# BusBreakout_I2C.net
KiCad netlist of a schematic drawn in EAGLE
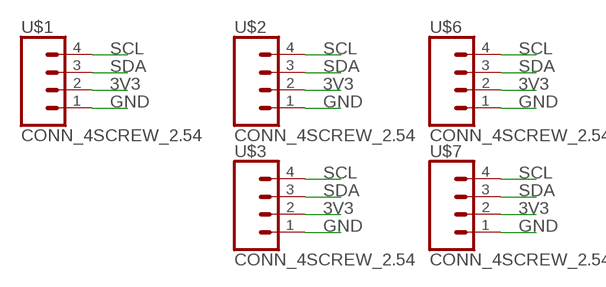
[diagram p0: schematic, sheet 1]

(export (version "E")
  (design (tool "Eeschema 10.0.6"))
  (components
    (comp (ref "U$1")
      (value "CONN_4SCREW_2.54")
      (footprint "eagle-import:1X04")
      (libsource (lib "eagle-import") (part "CONN_4SCREW_2.54"))
    )
    (comp (ref "U$2")
      (value "CONN_4SCREW_2.54")
      (footprint "eagle-import:1X04")
      (libsource (lib "eagle-import") (part "CONN_4SCREW_2.54"))
    )
    (comp (ref "U$3")
      (value "CONN_4SCREW_2.54")
      (footprint "eagle-import:1X04")
      (libsource (lib "eagle-import") (part "CONN_4SCREW_2.54"))
    )
    (comp (ref "U$6")
      (value "CONN_4SCREW_2.54")
      (footprint "eagle-import:1X04")
      (libsource (lib "eagle-import") (part "CONN_4SCREW_2.54"))
    )
    (comp (ref "U$7")
      (value "CONN_4SCREW_2.54")
      (footprint "eagle-import:1X04")
      (libsource (lib "eagle-import") (part "CONN_4SCREW_2.54"))
    )
  )
  (nets
    (net (code "1") (name "/3V3") (class "Default")
      (node (ref "U$1") (pin "2") (pinfunction "2_2") (pintype "passive"))
      (node (ref "U$2") (pin "2") (pinfunction "2_2") (pintype "passive"))
      (node (ref "U$3") (pin "2") (pinfunction "2_2") (pintype "passive"))
      (node (ref "U$6") (pin "2") (pinfunction "2_2") (pintype "passive"))
      (node (ref "U$7") (pin "2") (pinfunction "2_2") (pintype "passive"))
    )
    (net (code "2") (name "/GND") (class "Default")
      (node (ref "U$1") (pin "1") (pinfunction "1_1") (pintype "passive"))
      (node (ref "U$2") (pin "1") (pinfunction "1_1") (pintype "passive"))
      (node (ref "U$3") (pin "1") (pinfunction "1_1") (pintype "passive"))
      (node (ref "U$6") (pin "1") (pinfunction "1_1") (pintype "passive"))
      (node (ref "U$7") (pin "1") (pinfunction "1_1") (pintype "passive"))
    )
    (net (code "3") (name "/SCL") (class "Default")
      (node (ref "U$1") (pin "4") (pinfunction "4_4") (pintype "passive"))
      (node (ref "U$2") (pin "4") (pinfunction "4_4") (pintype "passive"))
      (node (ref "U$3") (pin "4") (pinfunction "4_4") (pintype "passive"))
      (node (ref "U$6") (pin "4") (pinfunction "4_4") (pintype "passive"))
      (node (ref "U$7") (pin "4") (pinfunction "4_4") (pintype "passive"))
    )
    (net (code "4") (name "/SDA") (class "Default")
      (node (ref "U$1") (pin "3") (pinfunction "3_3") (pintype "passive"))
      (node (ref "U$2") (pin "3") (pinfunction "3_3") (pintype "passive"))
      (node (ref "U$3") (pin "3") (pinfunction "3_3") (pintype "passive"))
      (node (ref "U$6") (pin "3") (pinfunction "3_3") (pintype "passive"))
      (node (ref "U$7") (pin "3") (pinfunction "3_3") (pintype "passive"))
    )
  )
)
